# schematic.net
KiCad netlist of a schematic drawn in Altium Designer
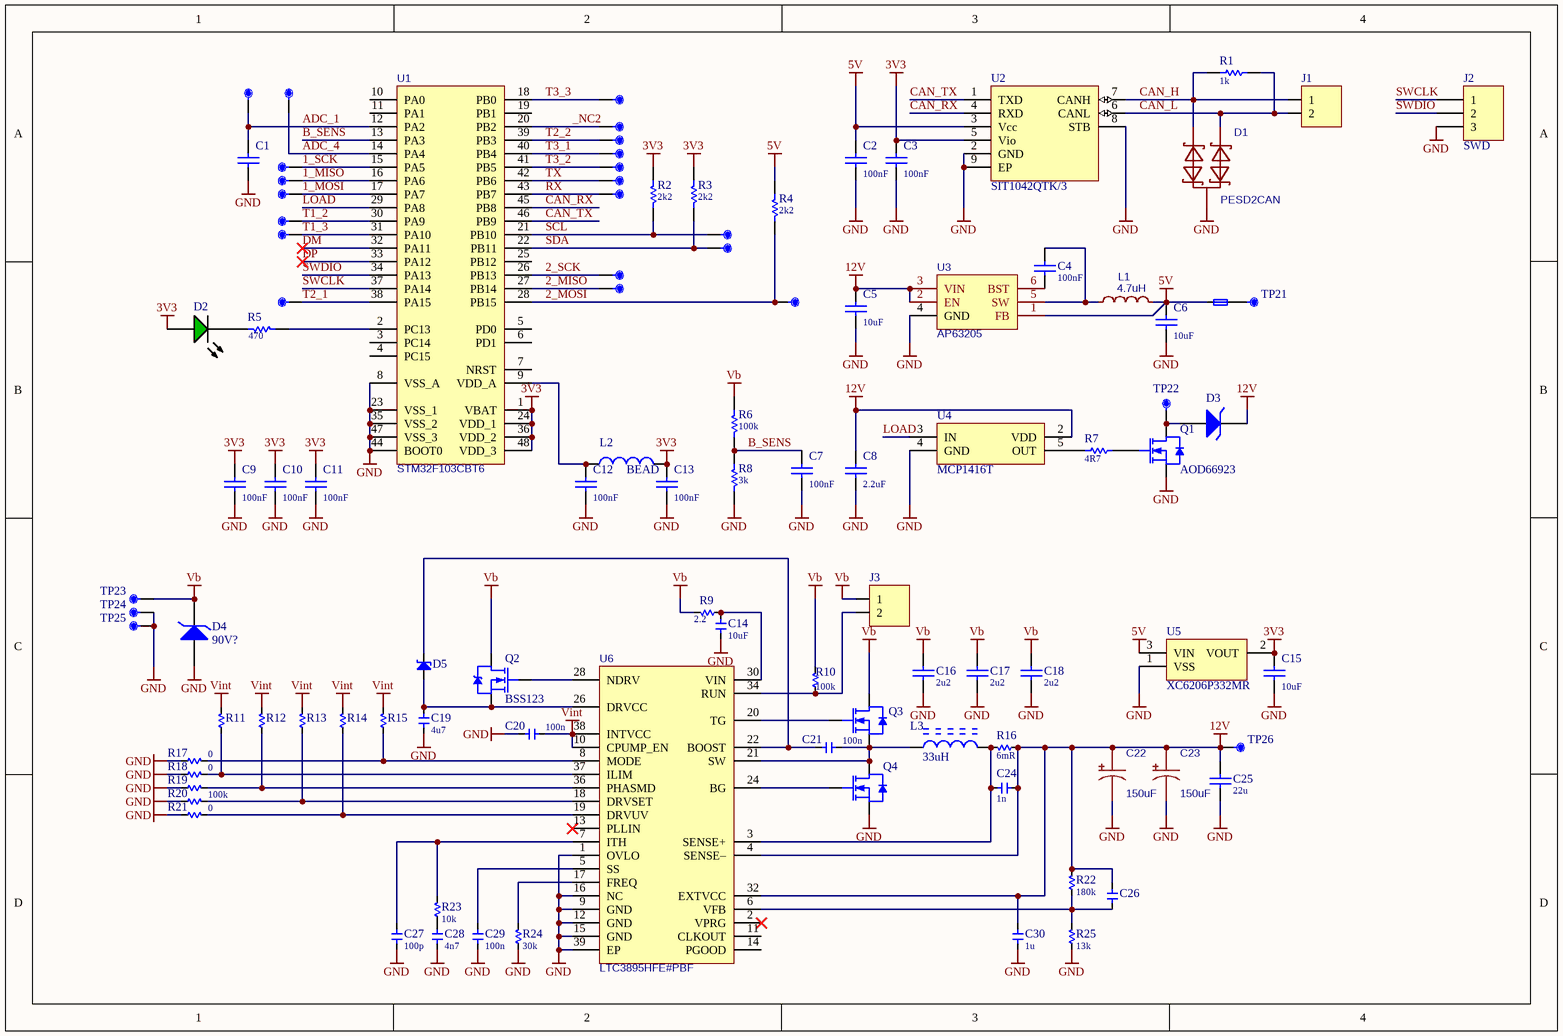
[diagram p0: schematic.SchDoc]

(export (version "E")
  (design (tool "Eeschema 10.0.6"))
  (components
    (comp (ref "C1")
      (value "100nF")
      (footprint "C0402")
      (libsource (lib "Miscellaneous Devices") (part "CAP"))
    )
    (comp (ref "C2")
      (value "100nF")
      (footprint "C0402")
      (fields (field (name "LCSC PART NUMBER") "C131394"))
      (libsource (lib "Miscellaneous Devices") (part "CAP"))
    )
    (comp (ref "C3")
      (value "100nF")
      (footprint "C0402")
      (fields (field (name "LCSC PART NUMBER") "C131394"))
      (libsource (lib "Miscellaneous Devices") (part "CAP"))
    )
    (comp (ref "C4")
      (value "100nF")
      (footprint "C0402")
      (libsource (lib "Miscellaneous Devices") (part "CAP"))
    )
    (comp (ref "C5")
      (value "10uF")
      (footprint "C1206")
      (fields (field (name "LCSC PART NUMBER") "C89632"))
      (libsource (lib "Miscellaneous Devices") (part "CAP"))
    )
    (comp (ref "C6")
      (value "10uF")
      (footprint "C1206")
      (fields (field (name "LCSC PART NUMBER") "C89632"))
      (libsource (lib "Miscellaneous Devices") (part "CAP"))
    )
    (comp (ref "C7")
      (value "100nF")
      (footprint "C0402")
      (libsource (lib "Miscellaneous Devices") (part "CAP"))
    )
    (comp (ref "C8")
      (value "2.2uF")
      (footprint "C0603")
      (fields (field (name "LCSC PART NUMBER") "C415535"))
      (libsource (lib "Miscellaneous Devices") (part "CAP"))
    )
    (comp (ref "C9")
      (value "100nF")
      (footprint "C0402")
      (libsource (lib "Miscellaneous Devices") (part "CAP"))
    )
    (comp (ref "C10")
      (value "100nF")
      (footprint "C0402")
      (libsource (lib "Miscellaneous Devices") (part "CAP"))
    )
    (comp (ref "C11")
      (value "100nF")
      (footprint "C0402")
      (libsource (lib "Miscellaneous Devices") (part "CAP"))
    )
    (comp (ref "C12")
      (value "100nF")
      (footprint "C0402")
      (libsource (lib "Miscellaneous Devices") (part "CAP"))
    )
    (comp (ref "C13")
      (value "100nF")
      (footprint "C0402")
      (libsource (lib "Miscellaneous Devices") (part "CAP"))
    )
    (comp (ref "C14")
      (value "10uF")
      (footprint "C0805")
      (fields (field (name "LCSC PART NUMBER") "C89632"))
      (libsource (lib "Schlib1") (part "CAP"))
    )
    (comp (ref "C15")
      (value "10uF")
      (footprint "C0603")
      (libsource (lib "Miscellaneous Devices") (part "CAP"))
    )
    (comp (ref "C16")
      (value "2u2")
      (footprint "C1210")
      (libsource (lib "Miscellaneous Devices") (part "CAP"))
    )
    (comp (ref "C17")
      (value "2u2")
      (footprint "C1210")
      (libsource (lib "Miscellaneous Devices") (part "CAP"))
    )
    (comp (ref "C18")
      (value "2u2")
      (footprint "C1210")
      (libsource (lib "Miscellaneous Devices") (part "CAP"))
    )
    (comp (ref "C19")
      (value "4u7")
      (footprint "C0805")
      (fields (field (name "LCSC PART NUMBER") "C89632"))
      (libsource (lib "Schlib1") (part "CAP"))
    )
    (comp (ref "C20")
      (value "100n")
      (footprint "C0603")
      (fields (field (name "LCSC PART NUMBER") "C89632"))
      (libsource (lib "Schlib1") (part "CAP"))
    )
    (comp (ref "C21")
      (value "100n")
      (footprint "C0603")
      (fields (field (name "LCSC PART NUMBER") "C89632"))
      (libsource (lib "Schlib1") (part "CAP"))
    )
    (comp (ref "C22")
      (value "150uF")
      (footprint "C7343")
      (libsource (lib "altium-import") (part "root_0_220uF_"))
    )
    (comp (ref "C23")
      (value "150uF")
      (footprint "C7343")
      (libsource (lib "altium-import") (part "root_0_220uF_"))
    )
    (comp (ref "C24")
      (value "1n")
      (footprint "C0402")
      (fields (field (name "LCSC PART NUMBER") "C89632"))
      (libsource (lib "Schlib1") (part "CAP"))
    )
    (comp (ref "C25")
      (value "22u")
      (footprint "C1210")
      (fields (field (name "LCSC PART NUMBER") "C778721"))
      (libsource (lib "Miscellaneous Devices") (part "CAP"))
    )
    (comp (ref "C26")
      (value "~")
      (footprint "C0402")
      (fields (field (name "LCSC PART NUMBER") "C89632"))
      (libsource (lib "Schlib1") (part "CAP"))
    )
    (comp (ref "C27")
      (value "100p")
      (footprint "C0402")
      (fields (field (name "LCSC PART NUMBER") "C89632"))
      (libsource (lib "Schlib1") (part "CAP"))
    )
    (comp (ref "C28")
      (value "4n7")
      (footprint "C0402")
      (fields (field (name "LCSC PART NUMBER") "C89632"))
      (libsource (lib "Schlib1") (part "CAP"))
    )
    (comp (ref "C29")
      (value "100n")
      (footprint "C0402")
      (fields (field (name "LCSC PART NUMBER") "C89632"))
      (libsource (lib "Schlib1") (part "CAP"))
    )
    (comp (ref "C30")
      (value "1u")
      (footprint "C0805")
      (fields (field (name "LCSC PART NUMBER") "C89632"))
      (libsource (lib "Schlib1") (part "CAP"))
    )
    (comp (ref "D1")
      (value "PESD2CAN")
      (footprint "SOT-23")
      (fields (field (name "LCSC PART NUMBER") "C5261081"))
      (libsource (lib "Miscellaneous Devices") (part "CDSOT23-SM712"))
    )
    (comp (ref "D2")
      (value "GRN")
      (footprint "LED-0603-GRN")
      (description "LED 0603 GRN")
      (libsource (lib "Miscellaneous Devices") (part "LED-0603-GREEN"))
    )
    (comp (ref "D3")
      (value "~")
      (footprint "SMC")
      (fields (field (name "LCSC PART NUMBER") "C693617"))
      (libsource (lib "Miscellaneous Devices") (part "NCP51460SN33T1G"))
    )
    (comp (ref "D4")
      (value "90V?")
      (footprint "SMC")
      (fields (field (name "LCSC PART NUMBER") "C693617"))
      (libsource (lib "Miscellaneous Devices") (part "NCP51460SN33T1G"))
    )
    (comp (ref "D5")
      (value "1N4148WS")
      (footprint "SOD-323")
      (fields (field (name "LCSC PART NUMBER") "C693617"))
      (libsource (lib "Schlib2") (part "NCP51460SN33T1G"))
    )
    (comp (ref "F1")
      (value "0.25A")
      (footprint "FUSE-1206")
      (fields (field (name "LCSC PART NUMBER") "C2924950"))
      (libsource (lib "Schlib1") (part "Fuse 1"))
    )
    (comp (ref "J1") (value "~") (footprint "HDR-1X2_2.54") (libsource (lib "Schlib1") (part "Header 2")))
    (comp (ref "J2")
      (value "SWD")
      (footprint "HDR-1x3-P1.25")
      (libsource (lib "Miscellaneous Devices") (part "Header 3"))
    )
    (comp (ref "J3") (value "~") (footprint "HDR-1x2-P1.25") (libsource (lib "Schlib1") (part "Header 2")))
    (comp (ref "L1")
      (value "4.7uH")
      (footprint "IND-SMD_L4.4-W4.2")
      (fields (field (name "LCSC PART NUMBER") "C167208"))
      (libsource (lib "altium-import") (part "root_0_4.7uH_"))
    )
    (comp (ref "L2")
      (value "BEAD")
      (footprint "L0402")
      (description "BEAD 0402")
      (libsource (lib "Miscellaneous Devices") (part "BLM18AG601SN1D"))
    )
    (comp (ref "L3")
      (value "33uH")
      (footprint "IND_10X11.5MM")
      (description "FXL1050-330-M")
      (libsource (lib "Miscellaneous Devices") (part "SRN3015-100M"))
    )
    (comp (ref "Q1")
      (value "AOD66923")
      (footprint "TO-252AA (DPAK)")
      (libsource (lib "Miscellaneous Devices") (part "2N7002"))
    )
    (comp (ref "Q2")
      (value "BSS123")
      (footprint "SOT-23")
      (description "HEXFET Power MOSFET")
      (libsource (lib "IR Discrete MOSFET - Power") (part "IRLML2402"))
    )
    (comp (ref "Q3")
      (value "AOD66923")
      (footprint "TO-252AA (DPAK)")
      (libsource (lib "Miscellaneous Devices") (part "2N7002"))
    )
    (comp (ref "Q4")
      (value "AOD66923")
      (footprint "TO-252AA (DPAK)")
      (libsource (lib "Miscellaneous Devices") (part "2N7002"))
    )
    (comp (ref "R1") (value "1k") (footprint "R1206") (libsource (lib "Miscellaneous Devices") (part "RES")))
    (comp (ref "R2") (value "2k2") (footprint "R0402") (libsource (lib "Miscellaneous Devices") (part "RES")))
    (comp (ref "R3") (value "2k2") (footprint "R0402") (libsource (lib "Miscellaneous Devices") (part "RES")))
    (comp (ref "R4") (value "2k2") (footprint "R0402") (libsource (lib "Miscellaneous Devices") (part "RES")))
    (comp (ref "R5") (value "470") (footprint "R0402") (libsource (lib "Miscellaneous Devices") (part "RES")))
    (comp (ref "R6")
      (value "100k")
      (footprint "R0603")
      (libsource (lib "Miscellaneous Devices") (part "RES"))
    )
    (comp (ref "R7")
      (value "4R7")
      (footprint "R0402")
      (fields (field (name "LCSC PART NUMBER") "C137862"))
      (libsource (lib "Miscellaneous Devices") (part "RES"))
    )
    (comp (ref "R8") (value "3k") (footprint "R0603") (libsource (lib "Miscellaneous Devices") (part "RES")))
    (comp (ref "R9") (value "2.2") (footprint "R0603") (libsource (lib "Schlib1") (part "RES")))
    (comp (ref "R10") (value "100k") (footprint "R0603") (libsource (lib "Schlib1") (part "RES")))
    (comp (ref "R11") (value "~") (footprint "R0603") (libsource (lib "Schlib1") (part "RES")))
    (comp (ref "R12") (value "~") (footprint "R0603") (libsource (lib "Schlib1") (part "RES")))
    (comp (ref "R13") (value "~") (footprint "R0603") (libsource (lib "Schlib1") (part "RES")))
    (comp (ref "R14") (value "~") (footprint "R0603") (libsource (lib "Schlib1") (part "RES")))
    (comp (ref "R15") (value "~") (footprint "R0603") (libsource (lib "Schlib1") (part "RES")))
    (comp (ref "R16") (value "6mR") (footprint "R2512-WIDE") (libsource (lib "Schlib1") (part "RES")))
    (comp (ref "R17") (value "0") (footprint "R0603") (libsource (lib "Schlib1") (part "RES")))
    (comp (ref "R18") (value "0") (footprint "R0603") (libsource (lib "Schlib1") (part "RES")))
    (comp (ref "R19") (value "~") (footprint "R0603") (libsource (lib "Schlib1") (part "RES")))
    (comp (ref "R20") (value "100k") (footprint "R0603") (libsource (lib "Schlib1") (part "RES")))
    (comp (ref "R21") (value "0") (footprint "R0603") (libsource (lib "Schlib1") (part "RES")))
    (comp (ref "R22") (value "180k") (footprint "R0603") (libsource (lib "Schlib1") (part "RES")))
    (comp (ref "R23") (value "10k") (footprint "R0603") (libsource (lib "Schlib1") (part "RES")))
    (comp (ref "R24") (value "30k") (footprint "R0603") (libsource (lib "Schlib1") (part "RES")))
    (comp (ref "R25") (value "13k") (footprint "R0603") (libsource (lib "Schlib1") (part "RES")))
    (comp (ref "TP1")
      (value "~")
      (footprint "TP_THT")
      (libsource (lib "Miscellaneous Devices") (part "TP_Dup1"))
    )
    (comp (ref "TP2")
      (value "~")
      (footprint "TP_THT")
      (libsource (lib "Miscellaneous Devices") (part "TP_Dup1"))
    )
    (comp (ref "TP3")
      (value "~")
      (footprint "TP_THT")
      (libsource (lib "Miscellaneous Devices") (part "TP_Dup1"))
    )
    (comp (ref "TP4")
      (value "~")
      (footprint "TP_THT")
      (libsource (lib "Miscellaneous Devices") (part "TP_Dup1"))
    )
    (comp (ref "TP5")
      (value "~")
      (footprint "TP_THT")
      (libsource (lib "Miscellaneous Devices") (part "TP_Dup1"))
    )
    (comp (ref "TP6")
      (value "~")
      (footprint "TP_THT")
      (libsource (lib "Miscellaneous Devices") (part "TP_Dup1"))
    )
    (comp (ref "TP7")
      (value "~")
      (footprint "TP_THT")
      (libsource (lib "Miscellaneous Devices") (part "TP_Dup1"))
    )
    (comp (ref "TP8")
      (value "~")
      (footprint "TP_THT")
      (libsource (lib "Miscellaneous Devices") (part "TP_Dup1"))
    )
    (comp (ref "TP9")
      (value "~")
      (footprint "TP_THT")
      (libsource (lib "Miscellaneous Devices") (part "TP_Dup1"))
    )
    (comp (ref "TP10")
      (value "~")
      (footprint "TP_THT")
      (libsource (lib "Miscellaneous Devices") (part "TP_Dup1"))
    )
    (comp (ref "TP11")
      (value "~")
      (footprint "TP_THT")
      (libsource (lib "Miscellaneous Devices") (part "TP_Dup1"))
    )
    (comp (ref "TP12")
      (value "~")
      (footprint "TP_THT")
      (libsource (lib "Miscellaneous Devices") (part "TP_Dup1"))
    )
    (comp (ref "TP13")
      (value "~")
      (footprint "TP_THT")
      (libsource (lib "Miscellaneous Devices") (part "TP_Dup1"))
    )
    (comp (ref "TP14")
      (value "~")
      (footprint "TP_THT")
      (libsource (lib "Miscellaneous Devices") (part "TP_Dup1"))
    )
    (comp (ref "TP15")
      (value "~")
      (footprint "TP_THT")
      (libsource (lib "Miscellaneous Devices") (part "TP_Dup1"))
    )
    (comp (ref "TP16")
      (value "~")
      (footprint "TP_THT")
      (libsource (lib "Miscellaneous Devices") (part "TP_Dup1"))
    )
    (comp (ref "TP17")
      (value "~")
      (footprint "TP_THT")
      (libsource (lib "Miscellaneous Devices") (part "TP_Dup1"))
    )
    (comp (ref "TP18")
      (value "~")
      (footprint "TP_THT")
      (libsource (lib "Miscellaneous Devices") (part "TP_Dup1"))
    )
    (comp (ref "TP19")
      (value "~")
      (footprint "TP_THT")
      (libsource (lib "Miscellaneous Devices") (part "TP_Dup1"))
    )
    (comp (ref "TP20")
      (value "~")
      (footprint "TP_THT")
      (libsource (lib "Miscellaneous Devices") (part "TP_Dup1"))
    )
    (comp (ref "TP21")
      (value "~")
      (footprint "TP_THT")
      (libsource (lib "Miscellaneous Devices") (part "TP_Dup1"))
    )
    (comp (ref "TP22")
      (value "~")
      (footprint "TP_THT")
      (libsource (lib "Miscellaneous Devices") (part "TP_Dup1"))
    )
    (comp (ref "TP23")
      (value "~")
      (footprint "TP_THT")
      (libsource (lib "Miscellaneous Devices") (part "TP_Dup1"))
    )
    (comp (ref "TP24")
      (value "~")
      (footprint "TP_THT")
      (libsource (lib "Miscellaneous Devices") (part "TP_Dup1"))
    )
    (comp (ref "TP25")
      (value "~")
      (footprint "TP_THT")
      (libsource (lib "Miscellaneous Devices") (part "TP_Dup1"))
    )
    (comp (ref "TP26")
      (value "~")
      (footprint "TP_THT")
      (libsource (lib "Miscellaneous Devices") (part "TP_Dup1"))
    )
    (comp (ref "U1")
      (value "STM32F103CBT6")
      (footprint "LQFP-48")
      (libsource (lib "Schlib1") (part "STM32F103CBT6"))
    )
    (comp (ref "U2")
      (value "SIT1042QTK/3")
      (footprint "DFN8_3X3_P065")
      (description "IC INTERFACE CAN")
      (fields (field (name "LCSC PART NUMBER") "C5308062"))
      (libsource (lib "Miscellaneous Devices") (part "LTC2875"))
    )
    (comp (ref "U3")
      (value "AP63205")
      (footprint "SOT-23-6")
      (fields (field (name "LCSC PART NUMBER") "C780769"))
      (libsource (lib "Schlib1") (part "AP63203WU-7"))
    )
    (comp (ref "U4")
      (value "MCP1416T")
      (footprint "SOT-23-5")
      (description "IC GATE DRVR LOW-SIDE SOT23")
      (fields (field (name "LCSC PART NUMBER") "C83775"))
      (libsource (lib "Schlib1") (part "FL3100T"))
    )
    (comp (ref "U5")
      (value "XC6206P332MR")
      (footprint "SOT-23")
      (libsource (lib "Schlib1") (part "Component_4_1"))
    )
    (comp (ref "U6")
      (value "LTC3895HFE#PBF")
      (footprint "TSSOP-38_L9.7-W4.4-P0.50-LS6.4-BL-EP-PE")
      (fields (field (name "LCSC PART NUMBER") "C580817"))
      (libsource (lib "lib_new2023") (part "LTC3895HFE#PBF"))
    )
  )
  (nets
    (net (code "1") (name "/1_MISO") (class "Default")
      (node (ref "TP9") (pin "1") (pinfunction "1_1") (pintype "passive"))
      (node (ref "U1") (pin "16") (pinfunction "PA6_16") (pintype "passive"))
    )
    (net (code "2") (name "/1_MOSI") (class "Default")
      (node (ref "TP11") (pin "1") (pinfunction "1_1") (pintype "passive"))
      (node (ref "U1") (pin "17") (pinfunction "PA7_17") (pintype "passive"))
    )
    (net (code "3") (name "/1_SCK") (class "Default")
      (node (ref "TP7") (pin "1") (pinfunction "1_1") (pintype "passive"))
      (node (ref "U1") (pin "15") (pinfunction "PA5_15") (pintype "passive"))
    )
    (net (code "4") (name "/2_MISO") (class "Default")
      (node (ref "TP18") (pin "1") (pinfunction "1_1") (pintype "passive"))
      (node (ref "U1") (pin "27") (pinfunction "PB14_27") (pintype "passive"))
    )
    (net (code "5") (name "/2_MOSI") (class "Default")
      (node (ref "R4") (pin "1") (pinfunction "1_1") (pintype "passive"))
      (node (ref "TP20") (pin "1") (pinfunction "1_1") (pintype "passive"))
      (node (ref "U1") (pin "28") (pinfunction "PB15_28") (pintype "passive"))
    )
    (net (code "6") (name "/2_SCK") (class "Default")
      (node (ref "TP17") (pin "1") (pinfunction "1_1") (pintype "passive"))
      (node (ref "U1") (pin "26") (pinfunction "PB13_26") (pintype "passive"))
    )
    (net (code "7") (name "/ADC_1") (class "Default")
      (node (ref "C1") (pin "2") (pinfunction "2_2") (pintype "passive"))
      (node (ref "TP1") (pin "1") (pinfunction "1_1") (pintype "passive"))
      (node (ref "U1") (pin "12") (pinfunction "PA2_12") (pintype "passive"))
    )
    (net (code "8") (name "/ADC_4") (class "Default")
      (node (ref "TP2") (pin "1") (pinfunction "1_1") (pintype "passive"))
      (node (ref "U1") (pin "14") (pinfunction "PA4_14") (pintype "passive"))
    )
    (net (code "9") (name "/B_SENS") (class "Default")
      (node (ref "C7") (pin "2") (pinfunction "2_2") (pintype "passive"))
      (node (ref "R6") (pin "1") (pinfunction "1_1") (pintype "passive"))
      (node (ref "R8") (pin "2") (pinfunction "2_2") (pintype "passive"))
      (node (ref "U1") (pin "13") (pinfunction "PA3_13") (pintype "passive"))
    )
    (net (code "10") (name "/CAN_H") (class "Default")
      (node (ref "D1") (pin "1") (pinfunction "1_1") (pintype "passive"))
      (node (ref "J1") (pin "1") (pinfunction "1_1") (pintype "passive"))
      (node (ref "R1") (pin "2") (pinfunction "2_2") (pintype "passive"))
      (node (ref "U2") (pin "7") (pinfunction "CANH_7") (pintype "bidirectional"))
    )
    (net (code "11") (name "/CAN_L") (class "Default")
      (node (ref "D1") (pin "2") (pinfunction "2_2") (pintype "passive"))
      (node (ref "J1") (pin "2") (pinfunction "2_2") (pintype "passive"))
      (node (ref "R1") (pin "1") (pinfunction "1_1") (pintype "passive"))
      (node (ref "U2") (pin "6") (pinfunction "CANL_6") (pintype "bidirectional"))
    )
    (net (code "12") (name "/CAN_RX") (class "Default")
      (node (ref "U1") (pin "45") (pinfunction "PB8_45") (pintype "passive"))
      (node (ref "U2") (pin "4") (pinfunction "RXD_4") (pintype "passive"))
    )
    (net (code "13") (name "/CAN_TX") (class "Default")
      (node (ref "U1") (pin "46") (pinfunction "PB9_46") (pintype "passive"))
      (node (ref "U2") (pin "1") (pinfunction "TXD_1") (pintype "passive"))
    )
    (net (code "14") (name "/DM") (class "Default")
      (node (ref "U1") (pin "32") (pinfunction "PA11_32") (pintype "passive+no_connect"))
    )
    (net (code "15") (name "/DP") (class "Default")
      (node (ref "U1") (pin "33") (pinfunction "PA12_33") (pintype "passive+no_connect"))
    )
    (net (code "16") (name "/LOAD") (class "Default")
      (node (ref "U1") (pin "29") (pinfunction "PA8_29") (pintype "passive"))
      (node (ref "U4") (pin "3") (pinfunction "IN_3") (pintype "passive"))
    )
    (net (code "17") (name "/RX") (class "Default")
      (node (ref "TP12") (pin "1") (pinfunction "1_1") (pintype "passive"))
      (node (ref "U1") (pin "43") (pinfunction "PB7_43") (pintype "passive"))
    )
    (net (code "18") (name "/SCL") (class "Default")
      (node (ref "R2") (pin "1") (pinfunction "1_1") (pintype "passive"))
      (node (ref "TP15") (pin "1") (pinfunction "1_1") (pintype "passive"))
      (node (ref "U1") (pin "21") (pinfunction "PB10_21") (pintype "passive"))
    )
    (net (code "19") (name "/SDA") (class "Default")
      (node (ref "R3") (pin "1") (pinfunction "1_1") (pintype "passive"))
      (node (ref "TP16") (pin "1") (pinfunction "1_1") (pintype "passive"))
      (node (ref "U1") (pin "22") (pinfunction "PB11_22") (pintype "passive"))
    )
    (net (code "20") (name "/SWCLK") (class "Default")
      (node (ref "J2") (pin "1") (pinfunction "1_1") (pintype "passive"))
      (node (ref "U1") (pin "37") (pinfunction "PA14_37") (pintype "passive"))
    )
    (net (code "21") (name "/SWDIO") (class "Default")
      (node (ref "J2") (pin "2") (pinfunction "2_2") (pintype "passive"))
      (node (ref "U1") (pin "34") (pinfunction "PA13_34") (pintype "passive"))
    )
    (net (code "22") (name "/T1_2") (class "Default")
      (node (ref "TP13") (pin "1") (pinfunction "1_1") (pintype "passive"))
      (node (ref "U1") (pin "30") (pinfunction "PA9_30") (pintype "passive"))
    )
    (net (code "23") (name "/T1_3") (class "Default")
      (node (ref "TP14") (pin "1") (pinfunction "1_1") (pintype "passive"))
      (node (ref "U1") (pin "31") (pinfunction "PA10_31") (pintype "passive"))
    )
    (net (code "24") (name "/T2_1") (class "Default")
      (node (ref "TP19") (pin "1") (pinfunction "1_1") (pintype "passive"))
      (node (ref "U1") (pin "38") (pinfunction "PA15_38") (pintype "passive"))
    )
    (net (code "25") (name "/T2_2") (class "Default")
      (node (ref "TP5") (pin "1") (pinfunction "1_1") (pintype "passive"))
      (node (ref "U1") (pin "39") (pinfunction "PB3_39") (pintype "passive"))
    )
    (net (code "26") (name "/T3_1") (class "Default")
      (node (ref "TP6") (pin "1") (pinfunction "1_1") (pintype "passive"))
      (node (ref "U1") (pin "40") (pinfunction "PB4_40") (pintype "passive"))
    )
    (net (code "27") (name "/T3_2") (class "Default")
      (node (ref "TP8") (pin "1") (pinfunction "1_1") (pintype "passive"))
      (node (ref "U1") (pin "41") (pinfunction "PB5_41") (pintype "passive"))
    )
    (net (code "28") (name "/T3_3") (class "Default")
      (node (ref "TP3") (pin "1") (pinfunction "1_1") (pintype "passive"))
      (node (ref "U1") (pin "18") (pinfunction "PB0_18") (pintype "passive"))
    )
    (net (code "29") (name "/TX") (class "Default")
      (node (ref "TP10") (pin "1") (pinfunction "1_1") (pintype "passive"))
      (node (ref "U1") (pin "42") (pinfunction "PB6_42") (pintype "passive"))
    )
    (net (code "30") (name "/_NC2") (class "Default")
      (node (ref "TP4") (pin "1") (pinfunction "1_1") (pintype "passive"))
      (node (ref "U1") (pin "20") (pinfunction "PB2_20") (pintype "passive"))
    )
    (net (code "31") (name "3V3") (class "Default")
      (node (ref "C10") (pin "2") (pinfunction "2_2") (pintype "passive"))
      (node (ref "C11") (pin "2") (pinfunction "2_2") (pintype "passive"))
      (node (ref "C13") (pin "2") (pinfunction "2_2") (pintype "passive"))
      (node (ref "C15") (pin "2") (pinfunction "2_2") (pintype "passive"))
      (node (ref "C3") (pin "2") (pinfunction "2_2") (pintype "passive"))
      (node (ref "C9") (pin "2") (pinfunction "2_2") (pintype "passive"))
      (node (ref "D2") (pin "1") (pinfunction "A_1") (pintype "passive"))
      (node (ref "L2") (pin "1") (pinfunction "1_1") (pintype "passive"))
      (node (ref "R2") (pin "2") (pinfunction "2_2") (pintype "passive"))
      (node (ref "R3") (pin "2") (pinfunction "2_2") (pintype "passive"))
      (node (ref "U1") (pin "1") (pinfunction "VBAT_1") (pintype "passive"))
      (node (ref "U1") (pin "24") (pinfunction "VDD_1_24") (pintype "passive"))
      (node (ref "U1") (pin "36") (pinfunction "VDD_2_36") (pintype "passive"))
      (node (ref "U1") (pin "48") (pinfunction "VDD_3_48") (pintype "passive"))
      (node (ref "U2") (pin "5") (pinfunction "Vio_5") (pintype "passive"))
      (node (ref "U5") (pin "2") (pinfunction "VOUT_2") (pintype "passive"))
    )
    (net (code "32") (name "5V") (class "Default")
      (node (ref "C2") (pin "2") (pinfunction "2_2") (pintype "passive"))
      (node (ref "C6") (pin "2") (pinfunction "2_2") (pintype "passive"))
      (node (ref "F1") (pin "2") (pinfunction "2_2") (pintype "passive"))
      (node (ref "L1") (pin "2") (pinfunction "2_2") (pintype "passive"))
      (node (ref "R4") (pin "2") (pinfunction "2_2") (pintype "passive"))
      (node (ref "U2") (pin "3") (pinfunction "Vcc_3") (pintype "passive"))
      (node (ref "U3") (pin "1") (pinfunction "FB_1") (pintype "passive"))
      (node (ref "U5") (pin "3") (pinfunction "VIN_3") (pintype "passive"))
    )
    (net (code "33") (name "12V") (class "Default")
      (node (ref "C22") (pin "1") (pinfunction "1_1") (pintype "passive"))
      (node (ref "C23") (pin "1") (pinfunction "1_1") (pintype "passive"))
      (node (ref "C24") (pin "1") (pinfunction "1_1") (pintype "passive"))
      (node (ref "C25") (pin "2") (pinfunction "2_2") (pintype "passive"))
      (node (ref "C26") (pin "1") (pinfunction "1_1") (pintype "passive"))
      (node (ref "C30") (pin "1") (pinfunction "1_1") (pintype "passive"))
      (node (ref "C5") (pin "2") (pinfunction "2_2") (pintype "passive"))
      (node (ref "C8") (pin "2") (pinfunction "2_2") (pintype "passive"))
      (node (ref "D3") (pin "2") (pinfunction "+_2") (pintype "passive"))
      (node (ref "R16") (pin "2") (pinfunction "2_2") (pintype "passive"))
      (node (ref "R22") (pin "1") (pinfunction "1_1") (pintype "passive"))
      (node (ref "TP26") (pin "1") (pinfunction "1_1") (pintype "passive"))
      (node (ref "U3") (pin "2") (pinfunction "EN_2") (pintype "passive"))
      (node (ref "U3") (pin "3") (pinfunction "VIN_3") (pintype "passive"))
      (node (ref "U4") (pin "2") (pinfunction "VDD_2") (pintype "passive"))
      (node (ref "U6") (pin "32") (pinfunction "EXTVCC_32") (pintype "passive"))
      (node (ref "U6") (pin "4") (pinfunction "SENSE–_4") (pintype "passive"))
    )
    (net (code "34") (name "GND") (class "Default")
      (node (ref "C1") (pin "1") (pinfunction "1_1") (pintype "passive"))
      (node (ref "C10") (pin "1") (pinfunction "1_1") (pintype "passive"))
      (node (ref "C11") (pin "1") (pinfunction "1_1") (pintype "passive"))
      (node (ref "C12") (pin "1") (pinfunction "1_1") (pintype "passive"))
      (node (ref "C13") (pin "1") (pinfunction "1_1") (pintype "passive"))
      (node (ref "C14") (pin "2") (pinfunction "2_2") (pintype "passive"))
      (node (ref "C15") (pin "1") (pinfunction "1_1") (pintype "passive"))
      (node (ref "C16") (pin "1") (pinfunction "1_1") (pintype "passive"))
      (node (ref "C17") (pin "1") (pinfunction "1_1") (pintype "passive"))
      (node (ref "C18") (pin "1") (pinfunction "1_1") (pintype "passive"))
      (node (ref "C19") (pin "2") (pinfunction "2_2") (pintype "passive"))
      (node (ref "C2") (pin "1") (pinfunction "1_1") (pintype "passive"))
      (node (ref "C20") (pin "1") (pinfunction "1_1") (pintype "passive"))
      (node (ref "C22") (pin "2") (pinfunction "2_2") (pintype "passive"))
      (node (ref "C23") (pin "2") (pinfunction "2_2") (pintype "passive"))
      (node (ref "C25") (pin "1") (pinfunction "1_1") (pintype "passive"))
      (node (ref "C27") (pin "2") (pinfunction "2_2") (pintype "passive"))
      (node (ref "C28") (pin "2") (pinfunction "2_2") (pintype "passive"))
      (node (ref "C29") (pin "2") (pinfunction "2_2") (pintype "passive"))
      (node (ref "C3") (pin "1") (pinfunction "1_1") (pintype "passive"))
      (node (ref "C30") (pin "2") (pinfunction "2_2") (pintype "passive"))
      (node (ref "C5") (pin "1") (pinfunction "1_1") (pintype "passive"))
      (node (ref "C6") (pin "1") (pinfunction "1_1") (pintype "passive"))
      (node (ref "C7") (pin "1") (pinfunction "1_1") (pintype "passive"))
      (node (ref "C8") (pin "1") (pinfunction "1_1") (pintype "passive"))
      (node (ref "C9") (pin "1") (pinfunction "1_1") (pintype "passive"))
      (node (ref "D1") (pin "3") (pinfunction "3_3") (pintype "passive"))
      (node (ref "D4") (pin "1") (pinfunction "-_1") (pintype "passive"))
      (node (ref "J2") (pin "3") (pinfunction "3_3") (pintype "passive"))
      (node (ref "Q1") (pin "3") (pinfunction "SOURCE_3") (pintype "passive"))
      (node (ref "Q4") (pin "3") (pinfunction "SOURCE_3") (pintype "passive"))
      (node (ref "R17") (pin "2") (pinfunction "2_2") (pintype "passive"))
      (node (ref "R18") (pin "2") (pinfunction "2_2") (pintype "passive"))
      (node (ref "R19") (pin "2") (pinfunction "2_2") (pintype "passive"))
      (node (ref "R20") (pin "2") (pinfunction "2_2") (pintype "passive"))
      (node (ref "R21") (pin "2") (pinfunction "2_2") (pintype "passive"))
      (node (ref "R24") (pin "2") (pinfunction "2_2") (pintype "passive"))
      (node (ref "R25") (pin "2") (pinfunction "2_2") (pintype "passive"))
      (node (ref "R8") (pin "1") (pinfunction "1_1") (pintype "passive"))
      (node (ref "TP24") (pin "1") (pinfunction "1_1") (pintype "passive"))
      (node (ref "TP25") (pin "1") (pinfunction "1_1") (pintype "passive"))
      (node (ref "U1") (pin "23") (pinfunction "VSS_1_23") (pintype "passive"))
      (node (ref "U1") (pin "35") (pinfunction "VSS_2_35") (pintype "passive"))
      (node (ref "U1") (pin "44") (pinfunction "BOOT0_44") (pintype "passive"))
      (node (ref "U1") (pin "47") (pinfunction "VSS_3_47") (pintype "passive"))
      (node (ref "U1") (pin "8") (pinfunction "VSS_A_8") (pintype "passive"))
      (node (ref "U2") (pin "2") (pinfunction "GND_2") (pintype "passive"))
      (node (ref "U2") (pin "8") (pinfunction "STB_8") (pintype "passive"))
      (node (ref "U2") (pin "9") (pinfunction "EP_9") (pintype "passive"))
      (node (ref "U3") (pin "4") (pinfunction "GND_4") (pintype "passive"))
      (node (ref "U4") (pin "4") (pinfunction "GND_4") (pintype "power_in"))
      (node (ref "U5") (pin "1") (pinfunction "VSS_1") (pintype "passive"))
      (node (ref "U6") (pin "1") (pinfunction "OVLO_1") (pintype "passive"))
      (node (ref "U6") (pin "12") (pinfunction "GND_12") (pintype "passive"))
      (node (ref "U6") (pin "15") (pinfunction "GND_15") (pintype "passive"))
      (node (ref "U6") (pin "16") (pinfunction "NC_16") (pintype "passive"))
      (node (ref "U6") (pin "39") (pinfunction "EP_39") (pintype "passive"))
      (node (ref "U6") (pin "9") (pinfunction "GND_9") (pintype "passive"))
    )
    (net (code "35") (name "Net-(C28-Pad1)") (class "Default")
      (node (ref "C28") (pin "1") (pinfunction "1_1") (pintype "passive"))
      (node (ref "R23") (pin "2") (pinfunction "2_2") (pintype "passive"))
    )
    (net (code "36") (name "Net-(D2-K)") (class "Default")
      (node (ref "D2") (pin "2") (pinfunction "K_2") (pintype "passive"))
      (node (ref "R5") (pin "1") (pinfunction "1_1") (pintype "passive"))
    )
    (net (code "37") (name "Net-(D3--)") (class "Default")
      (node (ref "D3") (pin "1") (pinfunction "-_1") (pintype "passive"))
      (node (ref "Q1") (pin "2") (pinfunction "DRAIN_2") (pintype "passive"))
      (node (ref "TP22") (pin "1") (pinfunction "1_1") (pintype "passive"))
    )
    (net (code "38") (name "Net-(D5-+)") (class "Default")
      (node (ref "C21") (pin "2") (pinfunction "2_2") (pintype "passive"))
      (node (ref "D5") (pin "2") (pinfunction "+_2") (pintype "passive"))
      (node (ref "U6") (pin "22") (pinfunction "BOOST_22") (pintype "passive"))
    )
    (net (code "39") (name "Net-(D5--)") (class "Default")
      (node (ref "C19") (pin "1") (pinfunction "1_1") (pintype "passive"))
      (node (ref "D5") (pin "1") (pinfunction "-_1") (pintype "passive"))
      (node (ref "Q2") (pin "2") (pinfunction "S_2") (pintype "passive"))
      (node (ref "U6") (pin "26") (pinfunction "DRVCC_26") (pintype "passive"))
    )
    (net (code "40") (name "Net-(F1-Pad1)") (class "Default")
      (node (ref "F1") (pin "1") (pinfunction "1_1") (pintype "passive"))
      (node (ref "TP21") (pin "1") (pinfunction "1_1") (pintype "passive"))
    )
    (net (code "41") (name "Net-(Q1-GATE)") (class "Default")
      (node (ref "Q1") (pin "1") (pinfunction "GATE_1") (pintype "passive"))
      (node (ref "R7") (pin "2") (pinfunction "2_2") (pintype "passive"))
    )
    (net (code "42") (name "Net-(Q2-G)") (class "Default")
      (node (ref "Q2") (pin "1") (pinfunction "G_1") (pintype "passive"))
      (node (ref "U6") (pin "28") (pinfunction "NDRV_28") (pintype "passive"))
    )
    (net (code "43") (name "Net-(Q3-GATE)") (class "Default")
      (node (ref "Q3") (pin "1") (pinfunction "GATE_1") (pintype "passive"))
      (node (ref "U6") (pin "20") (pinfunction "TG_20") (pintype "passive"))
    )
    (net (code "44") (name "Net-(Q3-SOURCE)") (class "Default")
      (node (ref "C21") (pin "1") (pinfunction "1_1") (pintype "passive"))
      (node (ref "L3") (pin "1") (pinfunction "1_1") (pintype "passive"))
      (node (ref "Q3") (pin "3") (pinfunction "SOURCE_3") (pintype "passive"))
      (node (ref "Q4") (pin "2") (pinfunction "DRAIN_2") (pintype "passive"))
      (node (ref "U6") (pin "21") (pinfunction "SW_21") (pintype "passive"))
    )
    (net (code "45") (name "Net-(Q4-GATE)") (class "Default")
      (node (ref "Q4") (pin "1") (pinfunction "GATE_1") (pintype "passive"))
      (node (ref "U6") (pin "24") (pinfunction "BG_24") (pintype "passive"))
    )
    (net (code "46") (name "Net-(U1-PC13)") (class "Default")
      (node (ref "R5") (pin "2") (pinfunction "2_2") (pintype "passive"))
      (node (ref "U1") (pin "2") (pinfunction "PC13_2") (pintype "passive"))
    )
    (net (code "47") (name "Net-(U1-VDD_A)") (class "Default")
      (node (ref "C12") (pin "2") (pinfunction "2_2") (pintype "passive"))
      (node (ref "L2") (pin "2") (pinfunction "2_2") (pintype "passive"))
      (node (ref "U1") (pin "9") (pinfunction "VDD_A_9") (pintype "passive"))
    )
    (net (code "48") (name "Net-(U3-BST)") (class "Default")
      (node (ref "C4") (pin "1") (pinfunction "1_1") (pintype "passive"))
      (node (ref "U3") (pin "6") (pinfunction "BST_6") (pintype "passive"))
    )
    (net (code "49") (name "Net-(U3-SW)") (class "Default")
      (node (ref "C4") (pin "2") (pinfunction "2_2") (pintype "passive"))
      (node (ref "L1") (pin "1") (pinfunction "1_1") (pintype "passive"))
      (node (ref "U3") (pin "5") (pinfunction "SW_5") (pintype "passive"))
    )
    (net (code "50") (name "Net-(U4-OUT)") (class "Default")
      (node (ref "R7") (pin "1") (pinfunction "1_1") (pintype "passive"))
      (node (ref "U4") (pin "5") (pinfunction "OUT_5") (pintype "passive"))
    )
    (net (code "51") (name "Net-(U6-DRVSET)") (class "Default")
      (node (ref "R13") (pin "2") (pinfunction "2_2") (pintype "passive"))
      (node (ref "R20") (pin "1") (pinfunction "1_1") (pintype "passive"))
      (node (ref "U6") (pin "18") (pinfunction "DRVSET_18") (pintype "passive"))
    )
    (net (code "52") (name "Net-(U6-DRVUV)") (class "Default")
      (node (ref "R14") (pin "2") (pinfunction "2_2") (pintype "passive"))
      (node (ref "R21") (pin "1") (pinfunction "1_1") (pintype "passive"))
      (node (ref "U6") (pin "19") (pinfunction "DRVUV_19") (pintype "passive"))
    )
    (net (code "53") (name "Net-(U6-FREQ)") (class "Default")
      (node (ref "R24") (pin "1") (pinfunction "1_1") (pintype "passive"))
      (node (ref "U6") (pin "17") (pinfunction "FREQ_17") (pintype "passive"))
    )
    (net (code "54") (name "Net-(U6-ILIM)") (class "Default")
      (node (ref "R11") (pin "2") (pinfunction "2_2") (pintype "passive"))
      (node (ref "R18") (pin "1") (pinfunction "1_1") (pintype "passive"))
      (node (ref "U6") (pin "37") (pinfunction "ILIM_37") (pintype "passive"))
    )
    (net (code "55") (name "Net-(U6-ITH)") (class "Default")
      (node (ref "C27") (pin "1") (pinfunction "1_1") (pintype "passive"))
      (node (ref "R23") (pin "1") (pinfunction "1_1") (pintype "passive"))
      (node (ref "U6") (pin "7") (pinfunction "ITH_7") (pintype "passive"))
    )
    (net (code "56") (name "Net-(U6-MODE)") (class "Default")
      (node (ref "R15") (pin "2") (pinfunction "2_2") (pintype "passive"))
      (node (ref "R17") (pin "1") (pinfunction "1_1") (pintype "passive"))
      (node (ref "U6") (pin "8") (pinfunction "MODE_8") (pintype "passive"))
    )
    (net (code "57") (name "Net-(U6-PHASMD)") (class "Default")
      (node (ref "R12") (pin "2") (pinfunction "2_2") (pintype "passive"))
      (node (ref "R19") (pin "1") (pinfunction "1_1") (pintype "passive"))
      (node (ref "U6") (pin "36") (pinfunction "PHASMD_36") (pintype "passive"))
    )
    (net (code "58") (name "Net-(U6-RUN)") (class "Default")
      (node (ref "J3") (pin "2") (pinfunction "2_2") (pintype "passive"))
      (node (ref "R10") (pin "2") (pinfunction "2_2") (pintype "passive"))
      (node (ref "U6") (pin "34") (pinfunction "RUN_34") (pintype "passive"))
    )
    (net (code "59") (name "Net-(U6-SENSE+)") (class "Default")
      (node (ref "C24") (pin "2") (pinfunction "2_2") (pintype "passive"))
      (node (ref "L3") (pin "2") (pinfunction "2_2") (pintype "passive"))
      (node (ref "R16") (pin "1") (pinfunction "1_1") (pintype "passive"))
      (node (ref "U6") (pin "3") (pinfunction "SENSE+_3") (pintype "passive"))
    )
    (net (code "60") (name "Net-(U6-SS)") (class "Default")
      (node (ref "C29") (pin "1") (pinfunction "1_1") (pintype "passive"))
      (node (ref "U6") (pin "5") (pinfunction "SS_5") (pintype "passive"))
    )
    (net (code "61") (name "Net-(U6-VFB)") (class "Default")
      (node (ref "C26") (pin "2") (pinfunction "2_2") (pintype "passive"))
      (node (ref "R22") (pin "2") (pinfunction "2_2") (pintype "passive"))
      (node (ref "R25") (pin "1") (pinfunction "1_1") (pintype "passive"))
      (node (ref "U6") (pin "6") (pinfunction "VFB_6") (pintype "passive"))
    )
    (net (code "62") (name "Net-(U6-VIN)") (class "Default")
      (node (ref "C14") (pin "1") (pinfunction "1_1") (pintype "passive"))
      (node (ref "R9") (pin "2") (pinfunction "2_2") (pintype "passive"))
      (node (ref "U6") (pin "30") (pinfunction "VIN_30") (pintype "passive"))
    )
    (net (code "63") (name "Vb") (class "Default")
      (node (ref "C16") (pin "2") (pinfunction "2_2") (pintype "passive"))
      (node (ref "C17") (pin "2") (pinfunction "2_2") (pintype "passive"))
      (node (ref "C18") (pin "2") (pinfunction "2_2") (pintype "passive"))
      (node (ref "D4") (pin "2") (pinfunction "+_2") (pintype "passive"))
      (node (ref "J3") (pin "1") (pinfunction "1_1") (pintype "passive"))
      (node (ref "Q2") (pin "3") (pinfunction "D_3") (pintype "passive"))
      (node (ref "Q3") (pin "2") (pinfunction "DRAIN_2") (pintype "passive"))
      (node (ref "R10") (pin "1") (pinfunction "1_1") (pintype "passive"))
      (node (ref "R6") (pin "2") (pinfunction "2_2") (pintype "passive"))
      (node (ref "R9") (pin "1") (pinfunction "1_1") (pintype "passive"))
      (node (ref "TP23") (pin "1") (pinfunction "1_1") (pintype "passive"))
    )
    (net (code "64") (name "Vint") (class "Default")
      (node (ref "C20") (pin "2") (pinfunction "2_2") (pintype "passive"))
      (node (ref "R11") (pin "1") (pinfunction "1_1") (pintype "passive"))
      (node (ref "R12") (pin "1") (pinfunction "1_1") (pintype "passive"))
      (node (ref "R13") (pin "1") (pinfunction "1_1") (pintype "passive"))
      (node (ref "R14") (pin "1") (pinfunction "1_1") (pintype "passive"))
      (node (ref "R15") (pin "1") (pinfunction "1_1") (pintype "passive"))
      (node (ref "U6") (pin "10") (pinfunction "CPUMP_EN_10") (pintype "passive"))
      (node (ref "U6") (pin "38") (pinfunction "INTVCC_38") (pintype "passive"))
    )
    (net (code "65") (name "unconnected-(U1-NRST-Pad7)") (class "Default")
      (node (ref "U1") (pin "7") (pinfunction "NRST_7") (pintype "passive"))
    )
    (net (code "66") (name "unconnected-(U1-PA0-Pad10)") (class "Default")
      (node (ref "U1") (pin "10") (pinfunction "PA0_10") (pintype "passive"))
    )
    (net (code "67") (name "unconnected-(U1-PA1-Pad11)") (class "Default")
      (node (ref "U1") (pin "11") (pinfunction "PA1_11") (pintype "passive"))
    )
    (net (code "68") (name "unconnected-(U1-PB1-Pad19)") (class "Default")
      (node (ref "U1") (pin "19") (pinfunction "PB1_19") (pintype "passive"))
    )
    (net (code "69") (name "unconnected-(U1-PB12-Pad25)") (class "Default")
      (node (ref "U1") (pin "25") (pinfunction "PB12_25") (pintype "passive"))
    )
    (net (code "70") (name "unconnected-(U1-PC14-Pad3)") (class "Default")
      (node (ref "U1") (pin "3") (pinfunction "PC14_3") (pintype "passive"))
    )
    (net (code "71") (name "unconnected-(U1-PC15-Pad4)") (class "Default")
      (node (ref "U1") (pin "4") (pinfunction "PC15_4") (pintype "passive"))
    )
    (net (code "72") (name "unconnected-(U1-PD0-Pad5)") (class "Default")
      (node (ref "U1") (pin "5") (pinfunction "PD0_5") (pintype "passive"))
    )
    (net (code "73") (name "unconnected-(U1-PD1-Pad6)") (class "Default")
      (node (ref "U1") (pin "6") (pinfunction "PD1_6") (pintype "passive"))
    )
    (net (code "74") (name "unconnected-(U6-CLKOUT-Pad11)") (class "Default")
      (node (ref "U6") (pin "11") (pinfunction "CLKOUT_11") (pintype "passive"))
    )
    (net (code "75") (name "unconnected-(U6-PGOOD-Pad14)") (class "Default")
      (node (ref "U6") (pin "14") (pinfunction "PGOOD_14") (pintype "passive"))
    )
    (net (code "76") (name "unconnected-(U6-PLLIN-Pad13)") (class "Default")
      (node (ref "U6") (pin "13") (pinfunction "PLLIN_13") (pintype "passive+no_connect"))
    )
    (net (code "77") (name "unconnected-(U6-VPRG-Pad2)") (class "Default")
      (node (ref "U6") (pin "2") (pinfunction "VPRG_2") (pintype "passive+no_connect"))
    )
  )
)
